# HF_Port.net
KiCad netlist of a schematic drawn in Altium Designer
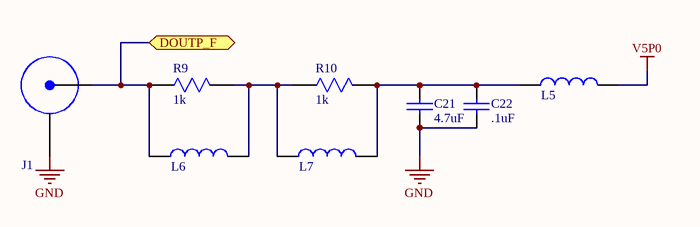
[diagram p0: HF_Port.SchDoc]

(export (version "E")
  (design (tool "Eeschema 10.0.6"))
  (components
    (comp (ref "C21")
      (value "4.7uF")
      (footprint "SMD Capacitor 0603")
      (libsource (lib "DA_Component_Library") (part "Capacitor"))
    )
    (comp (ref "C22")
      (value ".1uF")
      (footprint "SMD CAP 0402")
      (libsource (lib "DA_Component_Library") (part "Capacitor"))
    )
    (comp (ref "J1")
      (value "Coax Connector")
      (footprint "SSMCX Throughhole Molex")
      (libsource (lib "DA_Component_Library") (part "Coax Connector"))
    )
    (comp (ref "L5")
      (value "Ferrite Bead")
      (footprint "BLM18KG601SN1D")
      (libsource (lib "DA_Component_Library") (part "Ferrite Bead"))
    )
    (comp (ref "L6")
      (value "Ferrite Bead")
      (footprint "CIG21L4R7MNE")
      (libsource (lib "DA_Component_Library") (part "Ferrite Bead"))
    )
    (comp (ref "L7")
      (value "Ferrite Bead")
      (footprint "CBC3225T101MR")
      (libsource (lib "DA_Component_Library") (part "Ferrite Bead"))
    )
    (comp (ref "R9")
      (value "1k")
      (footprint "SMD RES 0402")
      (libsource (lib "DA_Component_Library") (part "Resistor"))
    )
    (comp (ref "R10")
      (value "1k")
      (footprint "SMD RES 0402")
      (libsource (lib "DA_Component_Library") (part "Resistor"))
    )
  )
  (nets
    (net (code "1") (name "/DOUTP_F") (class "Default")
      (node (ref "J1") (pin "0") (pinfunction "0_0") (pintype "passive"))
      (node (ref "L6") (pin "1") (pinfunction "1_1") (pintype "passive"))
      (node (ref "R9") (pin "0") (pinfunction "0_0") (pintype "passive"))
    )
    (net (code "2") (name "GND") (class "Default")
      (node (ref "C21") (pin "1") (pinfunction "1_1") (pintype "passive"))
      (node (ref "C22") (pin "1") (pinfunction "1_1") (pintype "passive"))
      (node (ref "J1") (pin "1") (pinfunction "1_1") (pintype "passive"))
    )
    (net (code "3") (name "Net-(C21-Pad0)") (class "Default")
      (node (ref "C21") (pin "0") (pinfunction "0_0") (pintype "passive"))
      (node (ref "C22") (pin "0") (pinfunction "0_0") (pintype "passive"))
      (node (ref "L5") (pin "1") (pinfunction "1_1") (pintype "passive"))
      (node (ref "L7") (pin "2") (pinfunction "2_2") (pintype "passive"))
      (node (ref "R10") (pin "1") (pinfunction "1_1") (pintype "passive"))
    )
    (net (code "4") (name "Net-(L6-Pad2)") (class "Default")
      (node (ref "L6") (pin "2") (pinfunction "2_2") (pintype "passive"))
      (node (ref "L7") (pin "1") (pinfunction "1_1") (pintype "passive"))
      (node (ref "R10") (pin "0") (pinfunction "0_0") (pintype "passive"))
      (node (ref "R9") (pin "1") (pinfunction "1_1") (pintype "passive"))
    )
    (net (code "5") (name "V5P0") (class "Default")
      (node (ref "L5") (pin "2") (pinfunction "2_2") (pintype "passive"))
    )
  )
)
